# NFC_Business_Card.net
KiCad netlist of a schematic drawn in Altium Designer
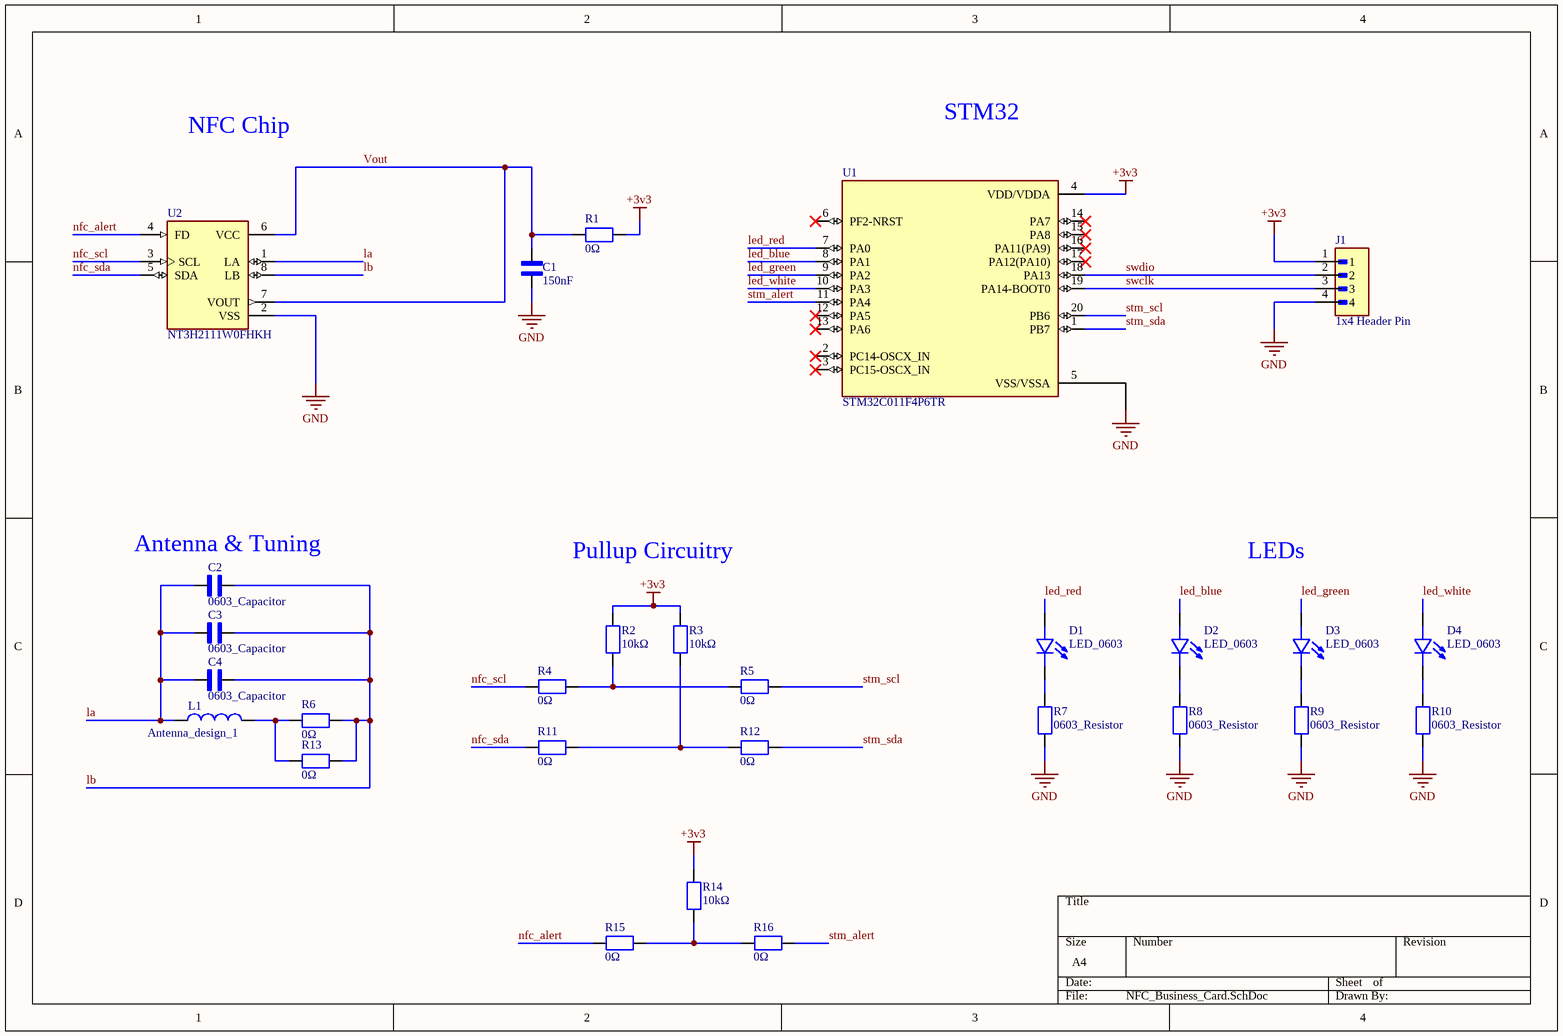
[diagram p0: NFC_Business_Card.SchDoc]

(export (version "E")
  (design (tool "Eeschema 10.0.6"))
  (components
    (comp (ref "C1")
      (value "150nF")
      (footprint "0603 PACKAGE")
      (libsource (lib "") (part "0603_Capacitor_1"))
    )
    (comp (ref "C2")
      (value "0603_Capacitor")
      (footprint "0603 PACKAGE")
      (libsource (lib "NFC_Business_Card") (part "0603_Capacitor"))
    )
    (comp (ref "C3")
      (value "0603_Capacitor")
      (footprint "0603 PACKAGE")
      (libsource (lib "NFC_Business_Card") (part "0603_Capacitor"))
    )
    (comp (ref "C4")
      (value "0603_Capacitor")
      (footprint "0603 PACKAGE")
      (libsource (lib "NFC_Business_Card") (part "0603_Capacitor"))
    )
    (comp (ref "D1")
      (value "LED_0603")
      (footprint "LED_KT-0603R")
      (description "Red 0603 Light Emitting Diodes")
      (fields (field (name "MF") "Hubei KENTO Elec") (field (name "MP") "KT-0603R"))
      (libsource (lib "NFC_Business_Card") (part "LED_0603"))
    )
    (comp (ref "D2")
      (value "LED_0603")
      (footprint "LED_KT-0603R")
      (description "Red 0603 Light Emitting Diodes")
      (fields (field (name "MF") "Hubei KENTO Elec") (field (name "MP") "KT-0603R"))
      (libsource (lib "NFC_Business_Card") (part "LED_0603"))
    )
    (comp (ref "D3")
      (value "LED_0603")
      (footprint "LED_KT-0603R")
      (description "Red 0603 Light Emitting Diodes")
      (fields (field (name "MF") "Hubei KENTO Elec") (field (name "MP") "KT-0603R"))
      (libsource (lib "NFC_Business_Card") (part "LED_0603"))
    )
    (comp (ref "D4")
      (value "LED_0603")
      (footprint "LED_KT-0603R")
      (description "Red 0603 Light Emitting Diodes")
      (fields (field (name "MF") "Hubei KENTO Elec") (field (name "MP") "KT-0603R"))
      (libsource (lib "NFC_Business_Card") (part "LED_0603"))
    )
    (comp (ref "J1")
      (value "1x4 Header Pin")
      (footprint "1x4 Jumper")
      (description "2.54mm (0.1) Pitch SIL Vertical Throughboard Pin Header, 7mm mating pin height, tin, 4 contacts")
      (fields (field (name "MF") "Harwin") (field (name "MP") "M20-9730446"))
      (libsource (lib "NFC_Business_Card") (part "1x4 Header Pin"))
    )
    (comp (ref "L1")
      (value "Antenna_design_1")
      (footprint "ANTENNA_DESIGN2")
      (libsource (lib "NFC_Business_Card") (part "Antenna_design_1"))
    )
    (comp (ref "R1")
      (value "0Ω")
      (footprint "0603 PACKAGE")
      (libsource (lib "NFC_Business_Card") (part "0603_Resistor"))
    )
    (comp (ref "R2")
      (value "10kΩ")
      (footprint "0603 PACKAGE")
      (libsource (lib "NFC_Business_Card") (part "0603_Resistor"))
    )
    (comp (ref "R3")
      (value "10kΩ")
      (footprint "0603 PACKAGE")
      (libsource (lib "NFC_Business_Card") (part "0603_Resistor"))
    )
    (comp (ref "R4")
      (value "0Ω")
      (footprint "0603 PACKAGE")
      (libsource (lib "NFC_Business_Card") (part "0603_Resistor"))
    )
    (comp (ref "R5")
      (value "0Ω")
      (footprint "0603 PACKAGE")
      (libsource (lib "NFC_Business_Card") (part "0603_Resistor"))
    )
    (comp (ref "R6")
      (value "0Ω")
      (footprint "0603 PACKAGE")
      (libsource (lib "NFC_Business_Card") (part "0603_Resistor"))
    )
    (comp (ref "R7")
      (value "0603_Resistor")
      (footprint "0603 PACKAGE")
      (libsource (lib "NFC_Business_Card") (part "0603_Resistor"))
    )
    (comp (ref "R8")
      (value "0603_Resistor")
      (footprint "0603 PACKAGE")
      (libsource (lib "NFC_Business_Card") (part "0603_Resistor"))
    )
    (comp (ref "R9")
      (value "0603_Resistor")
      (footprint "0603 PACKAGE")
      (libsource (lib "NFC_Business_Card") (part "0603_Resistor"))
    )
    (comp (ref "R10")
      (value "0603_Resistor")
      (footprint "0603 PACKAGE")
      (libsource (lib "NFC_Business_Card") (part "0603_Resistor"))
    )
    (comp (ref "R11")
      (value "0Ω")
      (footprint "0603 PACKAGE")
      (libsource (lib "NFC_Business_Card") (part "0603_Resistor"))
    )
    (comp (ref "R12")
      (value "0Ω")
      (footprint "0603 PACKAGE")
      (libsource (lib "NFC_Business_Card") (part "0603_Resistor"))
    )
    (comp (ref "R13")
      (value "0Ω")
      (footprint "0603 PACKAGE")
      (libsource (lib "NFC_Business_Card") (part "0603_Resistor"))
    )
    (comp (ref "R14")
      (value "10kΩ")
      (footprint "0603 PACKAGE")
      (libsource (lib "NFC_Business_Card") (part "0603_Resistor"))
    )
    (comp (ref "R15")
      (value "0Ω")
      (footprint "0603 PACKAGE")
      (libsource (lib "NFC_Business_Card") (part "0603_Resistor"))
    )
    (comp (ref "R16")
      (value "0Ω")
      (footprint "0603 PACKAGE")
      (libsource (lib "NFC_Business_Card") (part "0603_Resistor"))
    )
    (comp (ref "U1")
      (value "STM32C011F4P6TR")
      (footprint "SOP65P640X120-20N")
      (description "ARMÂ® CortexÂ®-M0+ STM32C0 Microcontroller IC 32-Bit 48MHz 16KB (16K x 8) FLASH 20-TSSOP")
      (fields (field (name "MF") "STMicroelectronics"))
      (libsource (lib "NFC_Business_Card") (part "STM32C011F4P6TR"))
    )
    (comp (ref "U2")
      (value "NT3H2111W0FHKH")
      (footprint "QFN8P50_160X160X50L40X20N")
      (description "RFID Reader/Transponder IC 13.56MHz ISO 14443, NFC IÂ²C 1.67V ~ 3.6V 8-XFQFN Exposed Pad")
      (fields (field (name "MF") "NXP USA"))
      (libsource (lib "NFC_Business_Card") (part "NT3H2111W0FHKH"))
    )
  )
  (nets
    (net (code "1") (name "+3v3") (class "Default")
      (node (ref "J1") (pin "1") (pinfunction "1_1") (pintype "passive"))
      (node (ref "R1") (pin "1") (pinfunction "1_1") (pintype "passive"))
      (node (ref "R14") (pin "1") (pinfunction "1_1") (pintype "passive"))
      (node (ref "R2") (pin "1") (pinfunction "1_1") (pintype "passive"))
      (node (ref "R3") (pin "1") (pinfunction "1_1") (pintype "passive"))
      (node (ref "U1") (pin "4") (pinfunction "VDD/VDDA_4") (pintype "power_in"))
    )
    (net (code "2") (name "/Vout") (class "Default")
      (node (ref "C1") (pin "2") (pinfunction "2_2") (pintype "passive"))
      (node (ref "R1") (pin "2") (pinfunction "2_2") (pintype "passive"))
      (node (ref "U2") (pin "6") (pinfunction "VCC_6") (pintype "power_in"))
      (node (ref "U2") (pin "7") (pinfunction "VOUT_7") (pintype "output"))
    )
    (net (code "3") (name "/la") (class "Default")
      (node (ref "C2") (pin "1") (pinfunction "1_1") (pintype "passive"))
      (node (ref "C3") (pin "1") (pinfunction "1_1") (pintype "passive"))
      (node (ref "C4") (pin "1") (pinfunction "1_1") (pintype "passive"))
      (node (ref "L1") (pin "1") (pinfunction "1_1") (pintype "passive"))
      (node (ref "U2") (pin "1") (pinfunction "LA_1") (pintype "bidirectional"))
    )
    (net (code "4") (name "/lb") (class "Default")
      (node (ref "C2") (pin "2") (pinfunction "2_2") (pintype "passive"))
      (node (ref "C3") (pin "2") (pinfunction "2_2") (pintype "passive"))
      (node (ref "C4") (pin "2") (pinfunction "2_2") (pintype "passive"))
      (node (ref "R13") (pin "1") (pinfunction "1_1") (pintype "passive"))
      (node (ref "R6") (pin "1") (pinfunction "1_1") (pintype "passive"))
      (node (ref "U2") (pin "8") (pinfunction "LB_8") (pintype "bidirectional"))
    )
    (net (code "5") (name "/led_blue") (class "Default")
      (node (ref "D2") (pin "A") (pinfunction "A_A") (pintype "passive"))
      (node (ref "U1") (pin "8") (pinfunction "PA1_8") (pintype "bidirectional"))
    )
    (net (code "6") (name "/led_green") (class "Default")
      (node (ref "D3") (pin "A") (pinfunction "A_A") (pintype "passive"))
      (node (ref "U1") (pin "9") (pinfunction "PA2_9") (pintype "bidirectional"))
    )
    (net (code "7") (name "/led_red") (class "Default")
      (node (ref "D1") (pin "A") (pinfunction "A_A") (pintype "passive"))
      (node (ref "U1") (pin "7") (pinfunction "PA0_7") (pintype "bidirectional"))
    )
    (net (code "8") (name "/led_white") (class "Default")
      (node (ref "D4") (pin "A") (pinfunction "A_A") (pintype "passive"))
      (node (ref "U1") (pin "10") (pinfunction "PA3_10") (pintype "bidirectional"))
    )
    (net (code "9") (name "/nfc_alert") (class "Default")
      (node (ref "R15") (pin "2") (pinfunction "2_2") (pintype "passive"))
      (node (ref "U2") (pin "4") (pinfunction "FD_4") (pintype "input"))
    )
    (net (code "10") (name "/nfc_scl") (class "Default")
      (node (ref "R4") (pin "2") (pinfunction "2_2") (pintype "passive"))
      (node (ref "U2") (pin "3") (pinfunction "SCL_3") (pintype "input"))
    )
    (net (code "11") (name "/nfc_sda") (class "Default")
      (node (ref "R11") (pin "2") (pinfunction "2_2") (pintype "passive"))
      (node (ref "U2") (pin "5") (pinfunction "SDA_5") (pintype "bidirectional"))
    )
    (net (code "12") (name "/stm_alert") (class "Default")
      (node (ref "R16") (pin "1") (pinfunction "1_1") (pintype "passive"))
      (node (ref "U1") (pin "11") (pinfunction "PA4_11") (pintype "bidirectional"))
    )
    (net (code "13") (name "/stm_scl") (class "Default")
      (node (ref "R5") (pin "1") (pinfunction "1_1") (pintype "passive"))
      (node (ref "U1") (pin "20") (pinfunction "PB6_20") (pintype "bidirectional"))
    )
    (net (code "14") (name "/stm_sda") (class "Default")
      (node (ref "R12") (pin "1") (pinfunction "1_1") (pintype "passive"))
      (node (ref "U1") (pin "1") (pinfunction "PB7_1") (pintype "bidirectional"))
    )
    (net (code "15") (name "/swclk") (class "Default")
      (node (ref "J1") (pin "3") (pinfunction "3_3") (pintype "passive"))
      (node (ref "U1") (pin "19") (pinfunction "PA14-BOOT0_19") (pintype "bidirectional"))
    )
    (net (code "16") (name "/swdio") (class "Default")
      (node (ref "J1") (pin "2") (pinfunction "2_2") (pintype "passive"))
      (node (ref "U1") (pin "18") (pinfunction "PA13_18") (pintype "bidirectional"))
    )
    (net (code "17") (name "GND") (class "Default")
      (node (ref "C1") (pin "1") (pinfunction "1_1") (pintype "passive"))
      (node (ref "J1") (pin "4") (pinfunction "4_4") (pintype "passive"))
      (node (ref "R10") (pin "1") (pinfunction "1_1") (pintype "passive"))
      (node (ref "R7") (pin "1") (pinfunction "1_1") (pintype "passive"))
      (node (ref "R8") (pin "1") (pinfunction "1_1") (pintype "passive"))
      (node (ref "R9") (pin "1") (pinfunction "1_1") (pintype "passive"))
      (node (ref "U1") (pin "5") (pinfunction "VSS/VSSA_5") (pintype "power_in"))
      (node (ref "U2") (pin "2") (pinfunction "VSS_2") (pintype "power_in"))
    )
    (net (code "18") (name "Net-(D1-PadC)") (class "Default")
      (node (ref "D1") (pin "C") (pinfunction "C_C") (pintype "passive"))
      (node (ref "R7") (pin "2") (pinfunction "2_2") (pintype "passive"))
    )
    (net (code "19") (name "Net-(D2-PadC)") (class "Default")
      (node (ref "D2") (pin "C") (pinfunction "C_C") (pintype "passive"))
      (node (ref "R8") (pin "2") (pinfunction "2_2") (pintype "passive"))
    )
    (net (code "20") (name "Net-(D3-PadC)") (class "Default")
      (node (ref "D3") (pin "C") (pinfunction "C_C") (pintype "passive"))
      (node (ref "R9") (pin "2") (pinfunction "2_2") (pintype "passive"))
    )
    (net (code "21") (name "Net-(D4-PadC)") (class "Default")
      (node (ref "D4") (pin "C") (pinfunction "C_C") (pintype "passive"))
      (node (ref "R10") (pin "2") (pinfunction "2_2") (pintype "passive"))
    )
    (net (code "22") (name "Net-(L1-Pad2)") (class "Default")
      (node (ref "L1") (pin "2") (pinfunction "2_2") (pintype "passive"))
      (node (ref "R13") (pin "2") (pinfunction "2_2") (pintype "passive"))
      (node (ref "R6") (pin "2") (pinfunction "2_2") (pintype "passive"))
    )
    (net (code "23") (name "Net-(R2-Pad2)") (class "Default")
      (node (ref "R2") (pin "2") (pinfunction "2_2") (pintype "passive"))
      (node (ref "R4") (pin "1") (pinfunction "1_1") (pintype "passive"))
      (node (ref "R5") (pin "2") (pinfunction "2_2") (pintype "passive"))
    )
    (net (code "24") (name "Net-(R11-Pad1)") (class "Default")
      (node (ref "R11") (pin "1") (pinfunction "1_1") (pintype "passive"))
      (node (ref "R12") (pin "2") (pinfunction "2_2") (pintype "passive"))
      (node (ref "R3") (pin "2") (pinfunction "2_2") (pintype "passive"))
    )
    (net (code "25") (name "Net-(R14-Pad2)") (class "Default")
      (node (ref "R14") (pin "2") (pinfunction "2_2") (pintype "passive"))
      (node (ref "R15") (pin "1") (pinfunction "1_1") (pintype "passive"))
      (node (ref "R16") (pin "2") (pinfunction "2_2") (pintype "passive"))
    )
    (net (code "26") (name "unconnected-(U1-PA5-Pad12)") (class "Default")
      (node (ref "U1") (pin "12") (pinfunction "PA5_12") (pintype "bidirectional+no_connect"))
    )
    (net (code "27") (name "unconnected-(U1-PA6-Pad13)") (class "Default")
      (node (ref "U1") (pin "13") (pinfunction "PA6_13") (pintype "bidirectional+no_connect"))
    )
    (net (code "28") (name "unconnected-(U1-PA7-Pad14)") (class "Default")
      (node (ref "U1") (pin "14") (pinfunction "PA7_14") (pintype "bidirectional+no_connect"))
    )
    (net (code "29") (name "unconnected-(U1-PA8-Pad15)") (class "Default")
      (node (ref "U1") (pin "15") (pinfunction "PA8_15") (pintype "bidirectional+no_connect"))
    )
    (net (code "30") (name "unconnected-(U1-PA11(PA9)-Pad16)") (class "Default")
      (node (ref "U1") (pin "16") (pinfunction "PA11(PA9)_16") (pintype "bidirectional+no_connect"))
    )
    (net (code "31") (name "unconnected-(U1-PA12(PA10)-Pad17)") (class "Default")
      (node (ref "U1") (pin "17") (pinfunction "PA12(PA10)_17") (pintype "bidirectional+no_connect"))
    )
    (net (code "32") (name "unconnected-(U1-PC14-OSCX_IN-Pad2)") (class "Default")
      (node (ref "U1") (pin "2") (pinfunction "PC14-OSCX_IN_2") (pintype "bidirectional+no_connect"))
    )
    (net (code "33") (name "unconnected-(U1-PC15-OSCX_IN-Pad3)") (class "Default")
      (node (ref "U1") (pin "3") (pinfunction "PC15-OSCX_IN_3") (pintype "bidirectional+no_connect"))
    )
    (net (code "34") (name "unconnected-(U1-PF2-NRST-Pad6)") (class "Default")
      (node (ref "U1") (pin "6") (pinfunction "PF2-NRST_6") (pintype "bidirectional+no_connect"))
    )
  )
)
